# 1DDR3L_16bits.net
KiCad netlist of a schematic drawn in Altium Designer
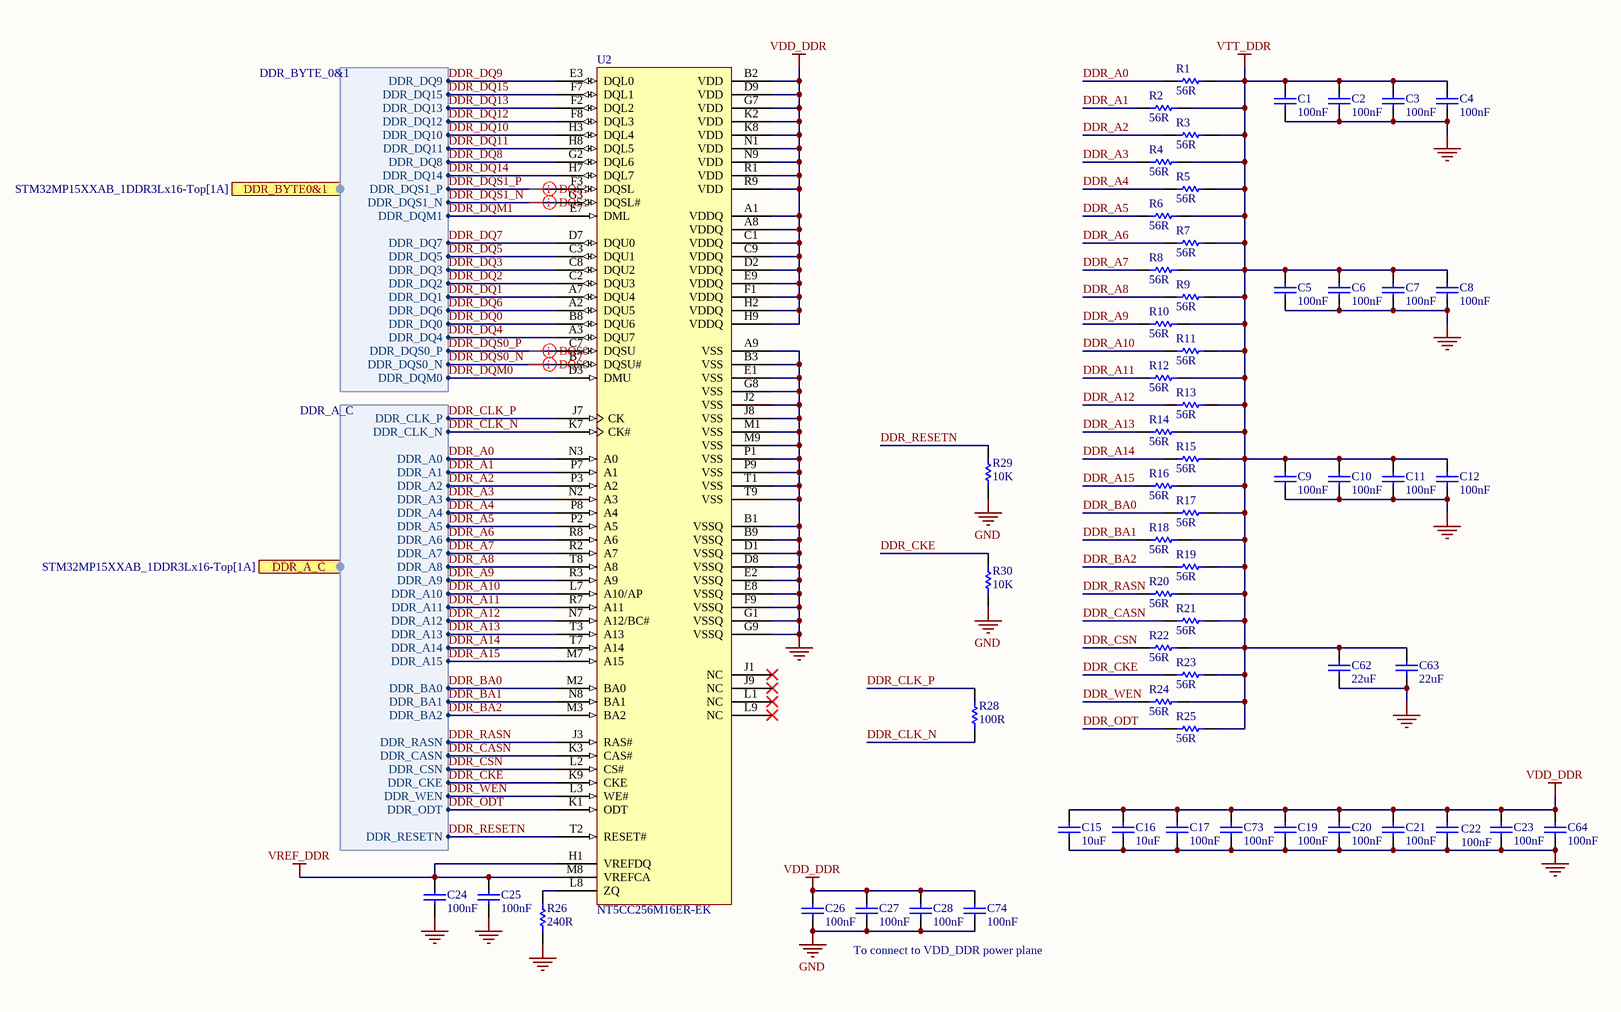
[diagram p0: 1DDR3L_16bits.SchDoc]

(export (version "E")
  (design (tool "Eeschema 10.0.6"))
  (components
    (comp (ref "C1")
      (value "100nF")
      (footprint "C0402")
      (description "Capacitor, MLCC, 100nF, 16V, X7R, 10%, 0402, T=0.5mm")
      (fields
        (field (name "INTERNAL_PART_NUMBER") "MCD-00006")
        (field (name "MANUFACTURER_PART_NUMBER") "CC0402KRX7R7BB104")
        (field (name "PROVIDED_BY") "SUBCO")
      )
      (libsource (lib "MCD_PARTS_database") (part "Capacitor"))
    )
    (comp (ref "C2")
      (value "100nF")
      (footprint "C0402")
      (description "Capacitor, MLCC, 100nF, 16V, X7R, 10%, 0402, T=0.5mm")
      (fields
        (field (name "INTERNAL_PART_NUMBER") "MCD-00006")
        (field (name "MANUFACTURER_PART_NUMBER") "CC0402KRX7R7BB104")
        (field (name "PROVIDED_BY") "SUBCO")
      )
      (libsource (lib "MCD_PARTS_database") (part "Capacitor"))
    )
    (comp (ref "C3")
      (value "100nF")
      (footprint "C0402")
      (description "Capacitor, MLCC, 100nF, 16V, X7R, 10%, 0402, T=0.5mm")
      (fields
        (field (name "INTERNAL_PART_NUMBER") "MCD-00006")
        (field (name "MANUFACTURER_PART_NUMBER") "CC0402KRX7R7BB104")
        (field (name "PROVIDED_BY") "SUBCO")
      )
      (libsource (lib "MCD_PARTS_database") (part "Capacitor"))
    )
    (comp (ref "C4")
      (value "100nF")
      (footprint "C0402")
      (description "Capacitor, MLCC, 100nF, 16V, X7R, 10%, 0402, T=0.5mm")
      (fields
        (field (name "INTERNAL_PART_NUMBER") "MCD-00006")
        (field (name "MANUFACTURER_PART_NUMBER") "CC0402KRX7R7BB104")
        (field (name "PROVIDED_BY") "SUBCO")
      )
      (libsource (lib "MCD_PARTS_database") (part "Capacitor"))
    )
    (comp (ref "C5")
      (value "100nF")
      (footprint "C0402")
      (description "Capacitor, MLCC, 100nF, 16V, X7R, 10%, 0402, T=0.5mm")
      (fields
        (field (name "INTERNAL_PART_NUMBER") "MCD-00006")
        (field (name "MANUFACTURER_PART_NUMBER") "CC0402KRX7R7BB104")
        (field (name "PROVIDED_BY") "SUBCO")
      )
      (libsource (lib "MCD_PARTS_database") (part "Capacitor"))
    )
    (comp (ref "C6")
      (value "100nF")
      (footprint "C0402")
      (description "Capacitor, MLCC, 100nF, 16V, X7R, 10%, 0402, T=0.5mm")
      (fields
        (field (name "INTERNAL_PART_NUMBER") "MCD-00006")
        (field (name "MANUFACTURER_PART_NUMBER") "CC0402KRX7R7BB104")
        (field (name "PROVIDED_BY") "SUBCO")
      )
      (libsource (lib "MCD_PARTS_database") (part "Capacitor"))
    )
    (comp (ref "C7")
      (value "100nF")
      (footprint "C0402")
      (description "Capacitor, MLCC, 100nF, 16V, X7R, 10%, 0402, T=0.5mm")
      (fields
        (field (name "INTERNAL_PART_NUMBER") "MCD-00006")
        (field (name "MANUFACTURER_PART_NUMBER") "CC0402KRX7R7BB104")
        (field (name "PROVIDED_BY") "SUBCO")
      )
      (libsource (lib "MCD_PARTS_database") (part "Capacitor"))
    )
    (comp (ref "C8")
      (value "100nF")
      (footprint "C0402")
      (description "Capacitor, MLCC, 100nF, 16V, X7R, 10%, 0402, T=0.5mm")
      (fields
        (field (name "INTERNAL_PART_NUMBER") "MCD-00006")
        (field (name "MANUFACTURER_PART_NUMBER") "CC0402KRX7R7BB104")
        (field (name "PROVIDED_BY") "SUBCO")
      )
      (libsource (lib "MCD_PARTS_database") (part "Capacitor"))
    )
    (comp (ref "C9")
      (value "100nF")
      (footprint "C0402")
      (description "Capacitor, MLCC, 100nF, 16V, X7R, 10%, 0402, T=0.5mm")
      (fields
        (field (name "INTERNAL_PART_NUMBER") "MCD-00006")
        (field (name "MANUFACTURER_PART_NUMBER") "CC0402KRX7R7BB104")
        (field (name "PROVIDED_BY") "SUBCO")
      )
      (libsource (lib "MCD_PARTS_database") (part "Capacitor"))
    )
    (comp (ref "C10")
      (value "100nF")
      (footprint "C0402")
      (description "Capacitor, MLCC, 100nF, 16V, X7R, 10%, 0402, T=0.5mm")
      (fields
        (field (name "INTERNAL_PART_NUMBER") "MCD-00006")
        (field (name "MANUFACTURER_PART_NUMBER") "CC0402KRX7R7BB104")
        (field (name "PROVIDED_BY") "SUBCO")
      )
      (libsource (lib "MCD_PARTS_database") (part "Capacitor"))
    )
    (comp (ref "C11")
      (value "100nF")
      (footprint "C0402")
      (description "Capacitor, MLCC, 100nF, 16V, X7R, 10%, 0402, T=0.5mm")
      (fields
        (field (name "INTERNAL_PART_NUMBER") "MCD-00006")
        (field (name "MANUFACTURER_PART_NUMBER") "CC0402KRX7R7BB104")
        (field (name "PROVIDED_BY") "SUBCO")
      )
      (libsource (lib "MCD_PARTS_database") (part "Capacitor"))
    )
    (comp (ref "C12")
      (value "100nF")
      (footprint "C0402")
      (description "Capacitor, MLCC, 100nF, 16V, X7R, 10%, 0402, T=0.5mm")
      (fields
        (field (name "INTERNAL_PART_NUMBER") "MCD-00006")
        (field (name "MANUFACTURER_PART_NUMBER") "CC0402KRX7R7BB104")
        (field (name "PROVIDED_BY") "SUBCO")
      )
      (libsource (lib "MCD_PARTS_database") (part "Capacitor"))
    )
    (comp (ref "C15")
      (value "10uF")
      (footprint "C0603")
      (description "Capacitor, MLCC, 10uF, 10V, X5R, 10%, 0603, T=0,8mm")
      (fields
        (field (name "INTERNAL_PART_NUMBER") "MCD-00099")
        (field (name "MANUFACTURER_PART_NUMBER") "GRM188R61A106KE69D")
        (field (name "PROVIDED_BY") "SUBCO")
      )
      (libsource (lib "MCD_PARTS_database") (part "Capacitor"))
    )
    (comp (ref "C16")
      (value "10uF")
      (footprint "C0603")
      (description "Capacitor, MLCC, 10uF, 10V, X5R, 10%, 0603, T=0,8mm")
      (fields
        (field (name "INTERNAL_PART_NUMBER") "MCD-00099")
        (field (name "MANUFACTURER_PART_NUMBER") "GRM188R61A106KE69D")
        (field (name "PROVIDED_BY") "SUBCO")
      )
      (libsource (lib "MCD_PARTS_database") (part "Capacitor"))
    )
    (comp (ref "C17")
      (value "100nF")
      (footprint "C0402")
      (description "Capacitor, MLCC, 100nF, 16V, X7R, 10%, 0402, T=0.5mm")
      (fields
        (field (name "INTERNAL_PART_NUMBER") "MCD-00006")
        (field (name "MANUFACTURER_PART_NUMBER") "CC0402KRX7R7BB104")
        (field (name "PROVIDED_BY") "SUBCO")
      )
      (libsource (lib "MCD_PARTS_database") (part "Capacitor"))
    )
    (comp (ref "C19")
      (value "100nF")
      (footprint "C0402")
      (description "Capacitor, MLCC, 100nF, 16V, X7R, 10%, 0402, T=0.5mm")
      (fields
        (field (name "INTERNAL_PART_NUMBER") "MCD-00006")
        (field (name "MANUFACTURER_PART_NUMBER") "CC0402KRX7R7BB104")
        (field (name "PROVIDED_BY") "SUBCO")
      )
      (libsource (lib "MCD_PARTS_database") (part "Capacitor"))
    )
    (comp (ref "C20")
      (value "100nF")
      (footprint "C0402")
      (description "Capacitor, MLCC, 100nF, 16V, X7R, 10%, 0402, T=0.5mm")
      (fields
        (field (name "INTERNAL_PART_NUMBER") "MCD-00006")
        (field (name "MANUFACTURER_PART_NUMBER") "CC0402KRX7R7BB104")
        (field (name "PROVIDED_BY") "SUBCO")
      )
      (libsource (lib "MCD_PARTS_database") (part "Capacitor"))
    )
    (comp (ref "C21")
      (value "100nF")
      (footprint "C0402")
      (description "Capacitor, MLCC, 100nF, 16V, X7R, 10%, 0402, T=0.5mm")
      (fields
        (field (name "INTERNAL_PART_NUMBER") "MCD-00006")
        (field (name "MANUFACTURER_PART_NUMBER") "CC0402KRX7R7BB104")
        (field (name "PROVIDED_BY") "SUBCO")
      )
      (libsource (lib "MCD_PARTS_database") (part "Capacitor"))
    )
    (comp (ref "C22")
      (value "100nF")
      (footprint "C0402")
      (description "Capacitor, MLCC, 100nF, 16V, X7R, 10%, 0402, T=0.5mm")
      (fields
        (field (name "INTERNAL_PART_NUMBER") "MCD-00006")
        (field (name "MANUFACTURER_PART_NUMBER") "CC0402KRX7R7BB104")
        (field (name "PROVIDED_BY") "SUBCO")
      )
      (libsource (lib "MCD_PARTS_database") (part "Capacitor"))
    )
    (comp (ref "C23")
      (value "100nF")
      (footprint "C0402")
      (description "Capacitor, MLCC, 100nF, 16V, X7R, 10%, 0402, T=0.5mm")
      (fields
        (field (name "INTERNAL_PART_NUMBER") "MCD-00006")
        (field (name "MANUFACTURER_PART_NUMBER") "CC0402KRX7R7BB104")
        (field (name "PROVIDED_BY") "SUBCO")
      )
      (libsource (lib "MCD_PARTS_database") (part "Capacitor"))
    )
    (comp (ref "C24")
      (value "100nF")
      (footprint "C0402")
      (description "Capacitor, MLCC, 100nF, 16V, X7R, 10%, 0402, T=0.5mm")
      (fields
        (field (name "INTERNAL_PART_NUMBER") "MCD-00006")
        (field (name "MANUFACTURER_PART_NUMBER") "CC0402KRX7R7BB104")
        (field (name "PROVIDED_BY") "SUBCO")
      )
      (libsource (lib "MCD_PARTS_database") (part "Capacitor"))
    )
    (comp (ref "C25")
      (value "100nF")
      (footprint "C0402")
      (description "Capacitor, MLCC, 100nF, 16V, X7R, 10%, 0402, T=0.5mm")
      (fields
        (field (name "INTERNAL_PART_NUMBER") "MCD-00006")
        (field (name "MANUFACTURER_PART_NUMBER") "CC0402KRX7R7BB104")
        (field (name "PROVIDED_BY") "SUBCO")
      )
      (libsource (lib "MCD_PARTS_database") (part "Capacitor"))
    )
    (comp (ref "C26")
      (value "100nF")
      (footprint "C0402")
      (description "Capacitor, MLCC, 100nF, 16V, X7R, 10%, 0402, T=0.5mm")
      (fields
        (field (name "INTERNAL_PART_NUMBER") "MCD-00006")
        (field (name "MANUFACTURER_PART_NUMBER") "CC0402KRX7R7BB104")
        (field (name "PROVIDED_BY") "SUBCO")
      )
      (libsource (lib "MCD_PARTS_database") (part "Capacitor"))
    )
    (comp (ref "C27")
      (value "100nF")
      (footprint "C0402")
      (description "Capacitor, MLCC, 100nF, 16V, X7R, 10%, 0402, T=0.5mm")
      (fields
        (field (name "INTERNAL_PART_NUMBER") "MCD-00006")
        (field (name "MANUFACTURER_PART_NUMBER") "CC0402KRX7R7BB104")
        (field (name "PROVIDED_BY") "SUBCO")
      )
      (libsource (lib "MCD_PARTS_database") (part "Capacitor"))
    )
    (comp (ref "C28")
      (value "100nF")
      (footprint "C0402")
      (description "Capacitor, MLCC, 100nF, 16V, X7R, 10%, 0402, T=0.5mm")
      (fields
        (field (name "INTERNAL_PART_NUMBER") "MCD-00006")
        (field (name "MANUFACTURER_PART_NUMBER") "CC0402KRX7R7BB104")
        (field (name "PROVIDED_BY") "SUBCO")
      )
      (libsource (lib "MCD_PARTS_database") (part "Capacitor"))
    )
    (comp (ref "C62")
      (value "22uF")
      (footprint "C0603")
      (description "Capacitor, MLCC, 22uF, 6V3, X5R, 20%, 0603, T=0,8mm")
      (fields
        (field (name "INTERNAL_PART_NUMBER") "MCD-00100")
        (field (name "MANUFACTURER_PART_NUMBER") "GRM188R60J226MEA0J")
        (field (name "PROVIDED_BY") "SUBCO")
      )
      (libsource (lib "MCD_PARTS_database") (part "Capacitor"))
    )
    (comp (ref "C63")
      (value "22uF")
      (footprint "C0603")
      (description "Capacitor, MLCC, 22uF, 6V3, X5R, 20%, 0603, T=0,8mm")
      (fields
        (field (name "INTERNAL_PART_NUMBER") "MCD-00100")
        (field (name "MANUFACTURER_PART_NUMBER") "GRM188R60J226MEA0J")
        (field (name "PROVIDED_BY") "SUBCO")
      )
      (libsource (lib "MCD_PARTS_database") (part "Capacitor"))
    )
    (comp (ref "C64")
      (value "100nF")
      (footprint "C0402")
      (description "Capacitor, MLCC, 100nF, 16V, X7R, 10%, 0402, T=0.5mm")
      (fields
        (field (name "INTERNAL_PART_NUMBER") "MCD-00006")
        (field (name "MANUFACTURER_PART_NUMBER") "CC0402KRX7R7BB104")
        (field (name "PROVIDED_BY") "SUBCO")
      )
      (libsource (lib "MCD_PARTS_database") (part "Capacitor"))
    )
    (comp (ref "C73")
      (value "100nF")
      (footprint "C0402")
      (description "Capacitor, MLCC, 100nF, 16V, X7R, 10%, 0402, T=0.5mm")
      (fields
        (field (name "INTERNAL_PART_NUMBER") "MCD-00006")
        (field (name "MANUFACTURER_PART_NUMBER") "CC0402KRX7R7BB104")
        (field (name "PROVIDED_BY") "SUBCO")
      )
      (libsource (lib "MCD_PARTS_database") (part "Capacitor"))
    )
    (comp (ref "C74")
      (value "100nF")
      (footprint "C0402")
      (description "Capacitor, MLCC, 100nF, 16V, X7R, 10%, 0402, T=0.5mm")
      (fields
        (field (name "INTERNAL_PART_NUMBER") "MCD-00006")
        (field (name "MANUFACTURER_PART_NUMBER") "CC0402KRX7R7BB104")
        (field (name "PROVIDED_BY") "SUBCO")
      )
      (libsource (lib "MCD_PARTS_database") (part "Capacitor"))
    )
    (comp (ref "R1")
      (value "56R")
      (footprint "R0402")
      (description "Resistor,56R,0402,1%,1/16W")
      (fields
        (field (name "INTERNAL_PART_NUMBER") "MCD-00118")
        (field (name "MANUFACTURER_PART_NUMBER") "RC0402FR-0756RL")
        (field (name "PROVIDED_BY") "SUBCO")
      )
      (libsource (lib "MCD_PARTS_database") (part "Resistor"))
    )
    (comp (ref "R2")
      (value "56R")
      (footprint "R0402")
      (description "Resistor,56R,0402,1%,1/16W")
      (fields
        (field (name "INTERNAL_PART_NUMBER") "MCD-00118")
        (field (name "MANUFACTURER_PART_NUMBER") "RC0402FR-0756RL")
        (field (name "PROVIDED_BY") "SUBCO")
      )
      (libsource (lib "MCD_PARTS_database") (part "Resistor"))
    )
    (comp (ref "R3")
      (value "56R")
      (footprint "R0402")
      (description "Resistor,56R,0402,1%,1/16W")
      (fields
        (field (name "INTERNAL_PART_NUMBER") "MCD-00118")
        (field (name "MANUFACTURER_PART_NUMBER") "RC0402FR-0756RL")
        (field (name "PROVIDED_BY") "SUBCO")
      )
      (libsource (lib "MCD_PARTS_database") (part "Resistor"))
    )
    (comp (ref "R4")
      (value "56R")
      (footprint "R0402")
      (description "Resistor,56R,0402,1%,1/16W")
      (fields
        (field (name "INTERNAL_PART_NUMBER") "MCD-00118")
        (field (name "MANUFACTURER_PART_NUMBER") "RC0402FR-0756RL")
        (field (name "PROVIDED_BY") "SUBCO")
      )
      (libsource (lib "MCD_PARTS_database") (part "Resistor"))
    )
    (comp (ref "R5")
      (value "56R")
      (footprint "R0402")
      (description "Resistor,56R,0402,1%,1/16W")
      (fields
        (field (name "INTERNAL_PART_NUMBER") "MCD-00118")
        (field (name "MANUFACTURER_PART_NUMBER") "RC0402FR-0756RL")
        (field (name "PROVIDED_BY") "SUBCO")
      )
      (libsource (lib "MCD_PARTS_database") (part "Resistor"))
    )
    (comp (ref "R6")
      (value "56R")
      (footprint "R0402")
      (description "Resistor,56R,0402,1%,1/16W")
      (fields
        (field (name "INTERNAL_PART_NUMBER") "MCD-00118")
        (field (name "MANUFACTURER_PART_NUMBER") "RC0402FR-0756RL")
        (field (name "PROVIDED_BY") "SUBCO")
      )
      (libsource (lib "MCD_PARTS_database") (part "Resistor"))
    )
    (comp (ref "R7")
      (value "56R")
      (footprint "R0402")
      (description "Resistor,56R,0402,1%,1/16W")
      (fields
        (field (name "INTERNAL_PART_NUMBER") "MCD-00118")
        (field (name "MANUFACTURER_PART_NUMBER") "RC0402FR-0756RL")
        (field (name "PROVIDED_BY") "SUBCO")
      )
      (libsource (lib "MCD_PARTS_database") (part "Resistor"))
    )
    (comp (ref "R8")
      (value "56R")
      (footprint "R0402")
      (description "Resistor,56R,0402,1%,1/16W")
      (fields
        (field (name "INTERNAL_PART_NUMBER") "MCD-00118")
        (field (name "MANUFACTURER_PART_NUMBER") "RC0402FR-0756RL")
        (field (name "PROVIDED_BY") "SUBCO")
      )
      (libsource (lib "MCD_PARTS_database") (part "Resistor"))
    )
    (comp (ref "R9")
      (value "56R")
      (footprint "R0402")
      (description "Resistor,56R,0402,1%,1/16W")
      (fields
        (field (name "INTERNAL_PART_NUMBER") "MCD-00118")
        (field (name "MANUFACTURER_PART_NUMBER") "RC0402FR-0756RL")
        (field (name "PROVIDED_BY") "SUBCO")
      )
      (libsource (lib "MCD_PARTS_database") (part "Resistor"))
    )
    (comp (ref "R10")
      (value "56R")
      (footprint "R0402")
      (description "Resistor,56R,0402,1%,1/16W")
      (fields
        (field (name "INTERNAL_PART_NUMBER") "MCD-00118")
        (field (name "MANUFACTURER_PART_NUMBER") "RC0402FR-0756RL")
        (field (name "PROVIDED_BY") "SUBCO")
      )
      (libsource (lib "MCD_PARTS_database") (part "Resistor"))
    )
    (comp (ref "R11")
      (value "56R")
      (footprint "R0402")
      (description "Resistor,56R,0402,1%,1/16W")
      (fields
        (field (name "INTERNAL_PART_NUMBER") "MCD-00118")
        (field (name "MANUFACTURER_PART_NUMBER") "RC0402FR-0756RL")
        (field (name "PROVIDED_BY") "SUBCO")
      )
      (libsource (lib "MCD_PARTS_database") (part "Resistor"))
    )
    (comp (ref "R12")
      (value "56R")
      (footprint "R0402")
      (description "Resistor,56R,0402,1%,1/16W")
      (fields
        (field (name "INTERNAL_PART_NUMBER") "MCD-00118")
        (field (name "MANUFACTURER_PART_NUMBER") "RC0402FR-0756RL")
        (field (name "PROVIDED_BY") "SUBCO")
      )
      (libsource (lib "MCD_PARTS_database") (part "Resistor"))
    )
    (comp (ref "R13")
      (value "56R")
      (footprint "R0402")
      (description "Resistor,56R,0402,1%,1/16W")
      (fields
        (field (name "INTERNAL_PART_NUMBER") "MCD-00118")
        (field (name "MANUFACTURER_PART_NUMBER") "RC0402FR-0756RL")
        (field (name "PROVIDED_BY") "SUBCO")
      )
      (libsource (lib "MCD_PARTS_database") (part "Resistor"))
    )
    (comp (ref "R14")
      (value "56R")
      (footprint "R0402")
      (description "Resistor,56R,0402,1%,1/16W")
      (fields
        (field (name "INTERNAL_PART_NUMBER") "MCD-00118")
        (field (name "MANUFACTURER_PART_NUMBER") "RC0402FR-0756RL")
        (field (name "PROVIDED_BY") "SUBCO")
      )
      (libsource (lib "MCD_PARTS_database") (part "Resistor"))
    )
    (comp (ref "R15")
      (value "56R")
      (footprint "R0402")
      (description "Resistor,56R,0402,1%,1/16W")
      (fields
        (field (name "INTERNAL_PART_NUMBER") "MCD-00118")
        (field (name "MANUFACTURER_PART_NUMBER") "RC0402FR-0756RL")
        (field (name "PROVIDED_BY") "SUBCO")
      )
      (libsource (lib "MCD_PARTS_database") (part "Resistor"))
    )
    (comp (ref "R16")
      (value "56R")
      (footprint "R0402")
      (description "Resistor,56R,0402,1%,1/16W")
      (fields
        (field (name "INTERNAL_PART_NUMBER") "MCD-00118")
        (field (name "MANUFACTURER_PART_NUMBER") "RC0402FR-0756RL")
        (field (name "PROVIDED_BY") "SUBCO")
      )
      (libsource (lib "MCD_PARTS_database") (part "Resistor"))
    )
    (comp (ref "R17")
      (value "56R")
      (footprint "R0402")
      (description "Resistor,56R,0402,1%,1/16W")
      (fields
        (field (name "INTERNAL_PART_NUMBER") "MCD-00118")
        (field (name "MANUFACTURER_PART_NUMBER") "RC0402FR-0756RL")
        (field (name "PROVIDED_BY") "SUBCO")
      )
      (libsource (lib "MCD_PARTS_database") (part "Resistor"))
    )
    (comp (ref "R18")
      (value "56R")
      (footprint "R0402")
      (description "Resistor,56R,0402,1%,1/16W")
      (fields
        (field (name "INTERNAL_PART_NUMBER") "MCD-00118")
        (field (name "MANUFACTURER_PART_NUMBER") "RC0402FR-0756RL")
        (field (name "PROVIDED_BY") "SUBCO")
      )
      (libsource (lib "MCD_PARTS_database") (part "Resistor"))
    )
    (comp (ref "R19")
      (value "56R")
      (footprint "R0402")
      (description "Resistor,56R,0402,1%,1/16W")
      (fields
        (field (name "INTERNAL_PART_NUMBER") "MCD-00118")
        (field (name "MANUFACTURER_PART_NUMBER") "RC0402FR-0756RL")
        (field (name "PROVIDED_BY") "SUBCO")
      )
      (libsource (lib "MCD_PARTS_database") (part "Resistor"))
    )
    (comp (ref "R20")
      (value "56R")
      (footprint "R0402")
      (description "Resistor,56R,0402,1%,1/16W")
      (fields
        (field (name "INTERNAL_PART_NUMBER") "MCD-00118")
        (field (name "MANUFACTURER_PART_NUMBER") "RC0402FR-0756RL")
        (field (name "PROVIDED_BY") "SUBCO")
      )
      (libsource (lib "MCD_PARTS_database") (part "Resistor"))
    )
    (comp (ref "R21")
      (value "56R")
      (footprint "R0402")
      (description "Resistor,56R,0402,1%,1/16W")
      (fields
        (field (name "INTERNAL_PART_NUMBER") "MCD-00118")
        (field (name "MANUFACTURER_PART_NUMBER") "RC0402FR-0756RL")
        (field (name "PROVIDED_BY") "SUBCO")
      )
      (libsource (lib "MCD_PARTS_database") (part "Resistor"))
    )
    (comp (ref "R22")
      (value "56R")
      (footprint "R0402")
      (description "Resistor,56R,0402,1%,1/16W")
      (fields
        (field (name "INTERNAL_PART_NUMBER") "MCD-00118")
        (field (name "MANUFACTURER_PART_NUMBER") "RC0402FR-0756RL")
        (field (name "PROVIDED_BY") "SUBCO")
      )
      (libsource (lib "MCD_PARTS_database") (part "Resistor"))
    )
    (comp (ref "R23")
      (value "56R")
      (footprint "R0402")
      (description "Resistor,56R,0402,1%,1/16W")
      (fields
        (field (name "INTERNAL_PART_NUMBER") "MCD-00118")
        (field (name "MANUFACTURER_PART_NUMBER") "RC0402FR-0756RL")
        (field (name "PROVIDED_BY") "SUBCO")
      )
      (libsource (lib "MCD_PARTS_database") (part "Resistor"))
    )
    (comp (ref "R24")
      (value "56R")
      (footprint "R0402")
      (description "Resistor,56R,0402,1%,1/16W")
      (fields
        (field (name "INTERNAL_PART_NUMBER") "MCD-00118")
        (field (name "MANUFACTURER_PART_NUMBER") "RC0402FR-0756RL")
        (field (name "PROVIDED_BY") "SUBCO")
      )
      (libsource (lib "MCD_PARTS_database") (part "Resistor"))
    )
    (comp (ref "R25")
      (value "56R")
      (footprint "R0402")
      (description "Resistor,56R,0402,1%,1/16W")
      (fields
        (field (name "INTERNAL_PART_NUMBER") "MCD-00118")
        (field (name "MANUFACTURER_PART_NUMBER") "RC0402FR-0756RL")
        (field (name "PROVIDED_BY") "SUBCO")
      )
      (libsource (lib "MCD_PARTS_database") (part "Resistor"))
    )
    (comp (ref "R26")
      (value "240R")
      (footprint "R0402")
      (description "Resistor,240R,0402,1%,1/16W")
      (fields
        (field (name "INTERNAL_PART_NUMBER") "MCD-00120")
        (field (name "MANUFACTURER_PART_NUMBER") "RC0402FR-07240RL")
        (field (name "PROVIDED_BY") "SUBCO")
      )
      (libsource (lib "MCD_PARTS_database") (part "Resistor"))
    )
    (comp (ref "R28")
      (value "100R")
      (footprint "R0402")
      (description "Resistor,100R,0402,1%,1/16W")
      (fields
        (field (name "INTERNAL_PART_NUMBER") "MCD-00119")
        (field (name "MANUFACTURER_PART_NUMBER") "RC0402FR-07100RL")
        (field (name "PROVIDED_BY") "SUBCO")
      )
      (libsource (lib "MCD_PARTS_database") (part "Resistor"))
    )
    (comp (ref "R29")
      (value "10K")
      (footprint "R0402")
      (description "Resistor,10K,0402,1%,1/16W")
      (fields
        (field (name "INTERNAL_PART_NUMBER") "MCD-00053")
        (field (name "MANUFACTURER_PART_NUMBER") "RC0402FR-0710KL")
        (field (name "PROVIDED_BY") "SUBCO")
      )
      (libsource (lib "MCD_PARTS_database") (part "Resistor"))
    )
    (comp (ref "R30")
      (value "10K")
      (footprint "R0402")
      (description "Resistor,10K,0402,1%,1/16W")
      (fields
        (field (name "INTERNAL_PART_NUMBER") "MCD-00053")
        (field (name "MANUFACTURER_PART_NUMBER") "RC0402FR-0710KL")
        (field (name "PROVIDED_BY") "SUBCO")
      )
      (libsource (lib "MCD_PARTS_database") (part "Resistor"))
    )
    (comp (ref "U2")
      (value "NT5CC256M16ER-EK")
      (footprint "ICC_VFBGA96_9x13_P080")
      (description "Memory,DDR3L,4Gb,256Mbx16,933Mhz,1V35,TFBGA")
      (fields
        (field (name "INTERNAL_PART_NUMBER") "MCD-01811")
        (field (name "MANUFACTURER") "NANYA")
        (field (name "PROVIDED_BY") "SUBCO")
      )
      (libsource (lib "MCD_PARTS_database") (part "NT5CC256M16ER-EK"))
    )
  )
  (nets
    (net (code "3") (name "/DDR_A0") (class "Default")
      (node (ref "R1") (pin "1") (pinfunction "1_1") (pintype "passive"))
      (node (ref "U2") (pin "N3") (pinfunction "A0_N3") (pintype "input"))
    )
    (net (code "4") (name "/DDR_A1") (class "Default")
      (node (ref "R2") (pin "1") (pinfunction "1_1") (pintype "passive"))
      (node (ref "U2") (pin "P7") (pinfunction "A1_P7") (pintype "input"))
    )
    (net (code "5") (name "/DDR_A2") (class "Default")
      (node (ref "R3") (pin "1") (pinfunction "1_1") (pintype "passive"))
      (node (ref "U2") (pin "P3") (pinfunction "A2_P3") (pintype "input"))
    )
    (net (code "6") (name "/DDR_A3") (class "Default")
      (node (ref "R4") (pin "1") (pinfunction "1_1") (pintype "passive"))
      (node (ref "U2") (pin "N2") (pinfunction "A3_N2") (pintype "input"))
    )
    (net (code "7") (name "/DDR_A4") (class "Default")
      (node (ref "R5") (pin "1") (pinfunction "1_1") (pintype "passive"))
      (node (ref "U2") (pin "P8") (pinfunction "A4_P8") (pintype "input"))
    )
    (net (code "8") (name "/DDR_A5") (class "Default")
      (node (ref "R6") (pin "1") (pinfunction "1_1") (pintype "passive"))
      (node (ref "U2") (pin "P2") (pinfunction "A5_P2") (pintype "input"))
    )
    (net (code "9") (name "/DDR_A6") (class "Default")
      (node (ref "R7") (pin "1") (pinfunction "1_1") (pintype "passive"))
      (node (ref "U2") (pin "R8") (pinfunction "A6_R8") (pintype "input"))
    )
    (net (code "10") (name "/DDR_A7") (class "Default")
      (node (ref "R8") (pin "1") (pinfunction "1_1") (pintype "passive"))
      (node (ref "U2") (pin "R2") (pinfunction "A7_R2") (pintype "input"))
    )
    (net (code "11") (name "/DDR_A8") (class "Default")
      (node (ref "R9") (pin "1") (pinfunction "1_1") (pintype "passive"))
      (node (ref "U2") (pin "T8") (pinfunction "A8_T8") (pintype "input"))
    )
    (net (code "12") (name "/DDR_A9") (class "Default")
      (node (ref "R10") (pin "1") (pinfunction "1_1") (pintype "passive"))
      (node (ref "U2") (pin "R3") (pinfunction "A9_R3") (pintype "input"))
    )
    (net (code "13") (name "/DDR_A10") (class "Default")
      (node (ref "R11") (pin "1") (pinfunction "1_1") (pintype "passive"))
      (node (ref "U2") (pin "L7") (pinfunction "A10/AP_L7") (pintype "input"))
    )
    (net (code "14") (name "/DDR_A11") (class "Default")
      (node (ref "R12") (pin "1") (pinfunction "1_1") (pintype "passive"))
      (node (ref "U2") (pin "R7") (pinfunction "A11_R7") (pintype "input"))
    )
    (net (code "15") (name "/DDR_A12") (class "Default")
      (node (ref "R13") (pin "1") (pinfunction "1_1") (pintype "passive"))
      (node (ref "U2") (pin "N7") (pinfunction "A12/BC#_N7") (pintype "input"))
    )
    (net (code "16") (name "/DDR_A13") (class "Default")
      (node (ref "R14") (pin "1") (pinfunction "1_1") (pintype "passive"))
      (node (ref "U2") (pin "T3") (pinfunction "A13_T3") (pintype "input"))
    )
    (net (code "17") (name "/DDR_A14") (class "Default")
      (node (ref "R15") (pin "1") (pinfunction "1_1") (pintype "passive"))
      (node (ref "U2") (pin "T7") (pinfunction "A14_T7") (pintype "input"))
    )
    (net (code "18") (name "/DDR_A15") (class "Default")
      (node (ref "R16") (pin "1") (pinfunction "1_1") (pintype "passive"))
      (node (ref "U2") (pin "M7") (pinfunction "A15_M7") (pintype "input"))
    )
    (net (code "19") (name "/DDR_BA0") (class "Default")
      (node (ref "R17") (pin "1") (pinfunction "1_1") (pintype "passive"))
      (node (ref "U2") (pin "M2") (pinfunction "BA0_M2") (pintype "input"))
    )
    (net (code "20") (name "/DDR_BA1") (class "Default")
      (node (ref "R18") (pin "1") (pinfunction "1_1") (pintype "passive"))
      (node (ref "U2") (pin "N8") (pinfunction "BA1_N8") (pintype "input"))
    )
    (net (code "21") (name "/DDR_BA2") (class "Default")
      (node (ref "R19") (pin "1") (pinfunction "1_1") (pintype "passive"))
      (node (ref "U2") (pin "M3") (pinfunction "BA2_M3") (pintype "input"))
    )
    (net (code "22") (name "/DDR_CASN") (class "Default")
      (node (ref "R21") (pin "1") (pinfunction "1_1") (pintype "passive"))
      (node (ref "U2") (pin "K3") (pinfunction "CAS#_K3") (pintype "input"))
    )
    (net (code "23") (name "/DDR_CKE") (class "Default")
      (node (ref "R23") (pin "1") (pinfunction "1_1") (pintype "passive"))
      (node (ref "R30") (pin "2") (pinfunction "2_2") (pintype "passive"))
      (node (ref "U2") (pin "K9") (pinfunction "CKE_K9") (pintype "input"))
    )
    (net (code "24") (name "/DDR_CLK_N") (class "Default")
      (node (ref "R28") (pin "1") (pinfunction "1_1") (pintype "passive"))
      (node (ref "U2") (pin "K7") (pinfunction "CK#_K7") (pintype "input"))
    )
    (net (code "25") (name "/DDR_CLK_P") (class "Default")
      (node (ref "R28") (pin "2") (pinfunction "2_2") (pintype "passive"))
      (node (ref "U2") (pin "J7") (pinfunction "CK_J7") (pintype "input"))
    )
    (net (code "26") (name "/DDR_CSN") (class "Default")
      (node (ref "R22") (pin "1") (pinfunction "1_1") (pintype "passive"))
      (node (ref "U2") (pin "L2") (pinfunction "CS#_L2") (pintype "input"))
    )
    (net (code "27") (name "/DDR_DQ0") (class "Default")
      (node (ref "U2") (pin "B8") (pinfunction "DQU6_B8") (pintype "bidirectional"))
    )
    (net (code "28") (name "/DDR_DQ1") (class "Default")
      (node (ref "U2") (pin "A7") (pinfunction "DQU4_A7") (pintype "bidirectional"))
    )
    (net (code "29") (name "/DDR_DQ2") (class "Default")
      (node (ref "U2") (pin "C2") (pinfunction "DQU3_C2") (pintype "bidirectional"))
    )
    (net (code "30") (name "/DDR_DQ3") (class "Default")
      (node (ref "U2") (pin "C8") (pinfunction "DQU2_C8") (pintype "bidirectional"))
    )
    (net (code "31") (name "/DDR_DQ4") (class "Default")
      (node (ref "U2") (pin "A3") (pinfunction "DQU7_A3") (pintype "bidirectional"))
    )
    (net (code "32") (name "/DDR_DQ5") (class "Default")
      (node (ref "U2") (pin "C3") (pinfunction "DQU1_C3") (pintype "bidirectional"))
    )
    (net (code "33") (name "/DDR_DQ6") (class "Default")
      (node (ref "U2") (pin "A2") (pinfunction "DQU5_A2") (pintype "bidirectional"))
    )
    (net (code "34") (name "/DDR_DQ7") (class "Default")
      (node (ref "U2") (pin "D7") (pinfunction "DQU0_D7") (pintype "bidirectional"))
    )
    (net (code "35") (name "/DDR_DQ8") (class "Default")
      (node (ref "U2") (pin "G2") (pinfunction "DQL6_G2") (pintype "bidirectional"))
    )
    (net (code "36") (name "/DDR_DQ9") (class "Default")
      (node (ref "U2") (pin "E3") (pinfunction "DQL0_E3") (pintype "bidirectional"))
    )
    (net (code "37") (name "/DDR_DQ10") (class "Default")
      (node (ref "U2") (pin "H3") (pinfunction "DQL4_H3") (pintype "bidirectional"))
    )
    (net (code "38") (name "/DDR_DQ11") (class "Default")
      (node (ref "U2") (pin "H8") (pinfunction "DQL5_H8") (pintype "bidirectional"))
    )
    (net (code "39") (name "/DDR_DQ12") (class "Default")
      (node (ref "U2") (pin "F8") (pinfunction "DQL3_F8") (pintype "bidirectional"))
    )
    (net (code "40") (name "/DDR_DQ13") (class "Default")
      (node (ref "U2") (pin "F2") (pinfunction "DQL2_F2") (pintype "bidirectional"))
    )
    (net (code "41") (name "/DDR_DQ14") (class "Default")
      (node (ref "U2") (pin "H7") (pinfunction "DQL7_H7") (pintype "bidirectional"))
    )
    (net (code "42") (name "/DDR_DQ15") (class "Default")
      (node (ref "U2") (pin "F7") (pinfunction "DQL1_F7") (pintype "bidirectional"))
    )
    (net (code "43") (name "/DDR_DQM0") (class "Default")
      (node (ref "U2") (pin "D3") (pinfunction "DMU_D3") (pintype "input"))
    )
    (net (code "44") (name "/DDR_DQM1") (class "Default")
      (node (ref "U2") (pin "E7") (pinfunction "DML_E7") (pintype "input"))
    )
    (net (code "45") (name "/DDR_DQS0_N") (class "Default")
      (node (ref "U2") (pin "B7") (pinfunction "DQSU#_B7") (pintype "bidirectional"))
    )
    (net (code "46") (name "/DDR_DQS0_P") (class "Default")
      (node (ref "U2") (pin "C7") (pinfunction "DQSU_C7") (pintype "bidirectional"))
    )
    (net (code "47") (name "/DDR_DQS1_N") (class "Default")
      (node (ref "U2") (pin "G3") (pinfunction "DQSL#_G3") (pintype "bidirectional"))
    )
    (net (code "48") (name "/DDR_DQS1_P") (class "Default")
      (node (ref "U2") (pin "F3") (pinfunction "DQSL_F3") (pintype "bidirectional"))
    )
    (net (code "49") (name "/DDR_ODT") (class "Default")
      (node (ref "R25") (pin "1") (pinfunction "1_1") (pintype "passive"))
      (node (ref "U2") (pin "K1") (pinfunction "ODT_K1") (pintype "input"))
    )
    (net (code "50") (name "/DDR_RASN") (class "Default")
      (node (ref "R20") (pin "1") (pinfunction "1_1") (pintype "passive"))
      (node (ref "U2") (pin "J3") (pinfunction "RAS#_J3") (pintype "input"))
    )
    (net (code "51") (name "/DDR_RESETN") (class "Default")
      (node (ref "R29") (pin "2") (pinfunction "2_2") (pintype "passive"))
      (node (ref "U2") (pin "T2") (pinfunction "RESET#_T2") (pintype "input"))
    )
    (net (code "52") (name "/DDR_WEN") (class "Default")
      (node (ref "R24") (pin "1") (pinfunction "1_1") (pintype "passive"))
      (node (ref "U2") (pin "L3") (pinfunction "WE#_L3") (pintype "input"))
    )
    (net (code "55") (name "GND") (class "Default")
      (node (ref "C1") (pin "1") (pinfunction "1_1") (pintype "passive"))
      (node (ref "C10") (pin "1") (pinfunction "1_1") (pintype "passive"))
      (node (ref "C11") (pin "1") (pinfunction "1_1") (pintype "passive"))
      (node (ref "C12") (pin "1") (pinfunction "1_1") (pintype "passive"))
      (node (ref "C15") (pin "1") (pinfunction "1_1") (pintype "passive"))
      (node (ref "C16") (pin "1") (pinfunction "1_1") (pintype "passive"))
      (node (ref "C17") (pin "1") (pinfunction "1_1") (pintype "passive"))
      (node (ref "C19") (pin "1") (pinfunction "1_1") (pintype "passive"))
      (node (ref "C2") (pin "1") (pinfunction "1_1") (pintype "passive"))
      (node (ref "C20") (pin "1") (pinfunction "1_1") (pintype "passive"))
      (node (ref "C21") (pin "1") (pinfunction "1_1") (pintype "passive"))
      (node (ref "C22") (pin "2") (pinfunction "2_2") (pintype "passive"))
      (node (ref "C23") (pin "1") (pinfunction "1_1") (pintype "passive"))
      (node (ref "C24") (pin "1") (pinfunction "1_1") (pintype "passive"))
      (node (ref "C25") (pin "1") (pinfunction "1_1") (pintype "passive"))
      (node (ref "C26") (pin "1") (pinfunction "1_1") (pintype "passive"))
      (node (ref "C27") (pin "1") (pinfunction "1_1") (pintype "passive"))
      (node (ref "C28") (pin "1") (pinfunction "1_1") (pintype "passive"))
      (node (ref "C3") (pin "1") (pinfunction "1_1") (pintype "passive"))
      (node (ref "C4") (pin "1") (pinfunction "1_1") (pintype "passive"))
      (node (ref "C5") (pin "1") (pinfunction "1_1") (pintype "passive"))
      (node (ref "C6") (pin "1") (pinfunction "1_1") (pintype "passive"))
      (node (ref "C62") (pin "1") (pinfunction "1_1") (pintype "passive"))
      (node (ref "C63") (pin "1") (pinfunction "1_1") (pintype "passive"))
      (node (ref "C64") (pin "1") (pinfunction "1_1") (pintype "passive"))
      (node (ref "C7") (pin "1") (pinfunction "1_1") (pintype "passive"))
      (node (ref "C73") (pin "1") (pinfunction "1_1") (pintype "passive"))
      (node (ref "C74") (pin "1") (pinfunction "1_1") (pintype "passive"))
      (node (ref "C8") (pin "1") (pinfunction "1_1") (pintype "passive"))
      (node (ref "C9") (pin "1") (pinfunction "1_1") (pintype "passive"))
      (node (ref "R26") (pin "1") (pinfunction "1_1") (pintype "passive"))
      (node (ref "R29") (pin "1") (pinfunction "1_1") (pintype "passive"))
      (node (ref "R30") (pin "1") (pinfunction "1_1") (pintype "passive"))
      (node (ref "U2") (pin "A9") (pinfunction "VSS_A9") (pintype "power_in"))
      (node (ref "U2") (pin "B1") (pinfunction "VSSQ_B1") (pintype "power_in"))
      (node (ref "U2") (pin "B3") (pinfunction "VSS_B3") (pintype "power_in"))
      (node (ref "U2") (pin "B9") (pinfunction "VSSQ_B9") (pintype "power_in"))
      (node (ref "U2") (pin "D1") (pinfunction "VSSQ_D1") (pintype "power_in"))
      (node (ref "U2") (pin "D8") (pinfunction "VSSQ_D8") (pintype "power_in"))
      (node (ref "U2") (pin "E1") (pinfunction "VSS_E1") (pintype "power_in"))
      (node (ref "U2") (pin "E2") (pinfunction "VSSQ_E2") (pintype "power_in"))
      (node (ref "U2") (pin "E8") (pinfunction "VSSQ_E8") (pintype "power_in"))
      (node (ref "U2") (pin "F9") (pinfunction "VSSQ_F9") (pintype "power_in"))
      (node (ref "U2") (pin "G1") (pinfunction "VSSQ_G1") (pintype "power_in"))
      (node (ref "U2") (pin "G8") (pinfunction "VSS_G8") (pintype "power_in"))
      (node (ref "U2") (pin "G9") (pinfunction "VSSQ_G9") (pintype "power_in"))
      (node (ref "U2") (pin "J2") (pinfunction "VSS_J2") (pintype "power_in"))
      (node (ref "U2") (pin "J8") (pinfunction "VSS_J8") (pintype "power_in"))
      (node (ref "U2") (pin "M1") (pinfunction "VSS_M1") (pintype "power_in"))
      (node (ref "U2") (pin "M9") (pinfunction "VSS_M9") (pintype "power_in"))
      (node (ref "U2") (pin "P1") (pinfunction "VSS_P1") (pintype "power_in"))
      (node (ref "U2") (pin "P9") (pinfunction "VSS_P9") (pintype "power_in"))
      (node (ref "U2") (pin "T1") (pinfunction "VSS_T1") (pintype "power_in"))
      (node (ref "U2") (pin "T9") (pinfunction "VSS_T9") (pintype "power_in"))
    )
    (net (code "56") (name "Net-(U2-ZQ)") (class "Default")
      (node (ref "R26") (pin "2") (pinfunction "2_2") (pintype "passive"))
      (node (ref "U2") (pin "L8") (pinfunction "ZQ_L8") (pintype "passive"))
    )
    (net (code "57") (name "VDD_DDR") (class "Default")
      (node (ref "C15") (pin "2") (pinfunction "2_2") (pintype "passive"))
      (node (ref "C16") (pin "2") (pinfunction "2_2") (pintype "passive"))
      (node (ref "C17") (pin "2") (pinfunction "2_2") (pintype "passive"))
      (node (ref "C19") (pin "2") (pinfunction "2_2") (pintype "passive"))
      (node (ref "C20") (pin "2") (pinfunction "2_2") (pintype "passive"))
      (node (ref "C21") (pin "2") (pinfunction "2_2") (pintype "passive"))
      (node (ref "C22") (pin "1") (pinfunction "1_1") (pintype "passive"))
      (node (ref "C23") (pin "2") (pinfunction "2_2") (pintype "passive"))
      (node (ref "C26") (pin "2") (pinfunction "2_2") (pintype "passive"))
      (node (ref "C27") (pin "2") (pinfunction "2_2") (pintype "passive"))
      (node (ref "C28") (pin "2") (pinfunction "2_2") (pintype "passive"))
      (node (ref "C64") (pin "2") (pinfunction "2_2") (pintype "passive"))
      (node (ref "C73") (pin "2") (pinfunction "2_2") (pintype "passive"))
      (node (ref "C74") (pin "2") (pinfunction "2_2") (pintype "passive"))
      (node (ref "U2") (pin "A1") (pinfunction "VDDQ_A1") (pintype "power_in"))
      (node (ref "U2") (pin "A8") (pinfunction "VDDQ_A8") (pintype "power_in"))
      (node (ref "U2") (pin "B2") (pinfunction "VDD_B2") (pintype "power_in"))
      (node (ref "U2") (pin "C1") (pinfunction "VDDQ_C1") (pintype "power_in"))
      (node (ref "U2") (pin "C9") (pinfunction "VDDQ_C9") (pintype "power_in"))
      (node (ref "U2") (pin "D2") (pinfunction "VDDQ_D2") (pintype "power_in"))
      (node (ref "U2") (pin "D9") (pinfunction "VDD_D9") (pintype "power_in"))
      (node (ref "U2") (pin "E9") (pinfunction "VDDQ_E9") (pintype "power_in"))
      (node (ref "U2") (pin "F1") (pinfunction "VDDQ_F1") (pintype "power_in"))
      (node (ref "U2") (pin "G7") (pinfunction "VDD_G7") (pintype "power_in"))
      (node (ref "U2") (pin "H2") (pinfunction "VDDQ_H2") (pintype "power_in"))
      (node (ref "U2") (pin "H9") (pinfunction "VDDQ_H9") (pintype "power_in"))
      (node (ref "U2") (pin "K2") (pinfunction "VDD_K2") (pintype "power_in"))
      (node (ref "U2") (pin "K8") (pinfunction "VDD_K8") (pintype "power_in"))
      (node (ref "U2") (pin "N1") (pinfunction "VDD_N1") (pintype "power_in"))
      (node (ref "U2") (pin "N9") (pinfunction "VDD_N9") (pintype "power_in"))
      (node (ref "U2") (pin "R1") (pinfunction "VDD_R1") (pintype "power_in"))
      (node (ref "U2") (pin "R9") (pinfunction "VDD_R9") (pintype "power_in"))
    )
    (net (code "58") (name "VREF_DDR") (class "Default")
      (node (ref "C24") (pin "2") (pinfunction "2_2") (pintype "passive"))
      (node (ref "C25") (pin "2") (pinfunction "2_2") (pintype "passive"))
      (node (ref "U2") (pin "H1") (pinfunction "VREFDQ_H1") (pintype "passive"))
      (node (ref "U2") (pin "M8") (pinfunction "VREFCA_M8") (pintype "passive"))
    )
    (net (code "59") (name "VTT_DDR") (class "Default")
      (node (ref "C1") (pin "2") (pinfunction "2_2") (pintype "passive"))
      (node (ref "C10") (pin "2") (pinfunction "2_2") (pintype "passive"))
      (node (ref "C11") (pin "2") (pinfunction "2_2") (pintype "passive"))
      (node (ref "C12") (pin "2") (pinfunction "2_2") (pintype "passive"))
      (node (ref "C2") (pin "2") (pinfunction "2_2") (pintype "passive"))
      (node (ref "C3") (pin "2") (pinfunction "2_2") (pintype "passive"))
      (node (ref "C4") (pin "2") (pinfunction "2_2") (pintype "passive"))
      (node (ref "C5") (pin "2") (pinfunction "2_2") (pintype "passive"))
      (node (ref "C6") (pin "2") (pinfunction "2_2") (pintype "passive"))
      (node (ref "C62") (pin "2") (pinfunction "2_2") (pintype "passive"))
      (node (ref "C63") (pin "2") (pinfunction "2_2") (pintype "passive"))
      (node (ref "C7") (pin "2") (pinfunction "2_2") (pintype "passive"))
      (node (ref "C8") (pin "2") (pinfunction "2_2") (pintype "passive"))
      (node (ref "C9") (pin "2") (pinfunction "2_2") (pintype "passive"))
      (node (ref "R1") (pin "2") (pinfunction "2_2") (pintype "passive"))
      (node (ref "R10") (pin "2") (pinfunction "2_2") (pintype "passive"))
      (node (ref "R11") (pin "2") (pinfunction "2_2") (pintype "passive"))
      (node (ref "R12") (pin "2") (pinfunction "2_2") (pintype "passive"))
      (node (ref "R13") (pin "2") (pinfunction "2_2") (pintype "passive"))
      (node (ref "R14") (pin "2") (pinfunction "2_2") (pintype "passive"))
      (node (ref "R15") (pin "2") (pinfunction "2_2") (pintype "passive"))
      (node (ref "R16") (pin "2") (pinfunction "2_2") (pintype "passive"))
      (node (ref "R17") (pin "2") (pinfunction "2_2") (pintype "passive"))
      (node (ref "R18") (pin "2") (pinfunction "2_2") (pintype "passive"))
      (node (ref "R19") (pin "2") (pinfunction "2_2") (pintype "passive"))
      (node (ref "R2") (pin "2") (pinfunction "2_2") (pintype "passive"))
      (node (ref "R20") (pin "2") (pinfunction "2_2") (pintype "passive"))
      (node (ref "R21") (pin "2") (pinfunction "2_2") (pintype "passive"))
      (node (ref "R22") (pin "2") (pinfunction "2_2") (pintype "passive"))
      (node (ref "R23") (pin "2") (pinfunction "2_2") (pintype "passive"))
      (node (ref "R24") (pin "2") (pinfunction "2_2") (pintype "passive"))
      (node (ref "R25") (pin "2") (pinfunction "2_2") (pintype "passive"))
      (node (ref "R3") (pin "2") (pinfunction "2_2") (pintype "passive"))
      (node (ref "R4") (pin "2") (pinfunction "2_2") (pintype "passive"))
      (node (ref "R5") (pin "2") (pinfunction "2_2") (pintype "passive"))
      (node (ref "R6") (pin "2") (pinfunction "2_2") (pintype "passive"))
      (node (ref "R7") (pin "2") (pinfunction "2_2") (pintype "passive"))
      (node (ref "R8") (pin "2") (pinfunction "2_2") (pintype "passive"))
      (node (ref "R9") (pin "2") (pinfunction "2_2") (pintype "passive"))
    )
    (net (code "60") (name "unconnected-(U2-NC-PadJ1)") (class "Default")
      (node (ref "U2") (pin "J1") (pinfunction "NC_J1") (pintype "passive+no_connect"))
    )
    (net (code "61") (name "unconnected-(U2-NC-PadJ9)") (class "Default")
      (node (ref "U2") (pin "J9") (pinfunction "NC_J9") (pintype "passive+no_connect"))
    )
    (net (code "62") (name "unconnected-(U2-NC-PadL1)") (class "Default")
      (node (ref "U2") (pin "L1") (pinfunction "NC_L1") (pintype "passive+no_connect"))
    )
    (net (code "63") (name "unconnected-(U2-NC-PadL9)") (class "Default")
      (node (ref "U2") (pin "L9") (pinfunction "NC_L9") (pintype "passive+no_connect"))
    )
  )
)
